# TempProbe.net
KiCad netlist of a schematic drawn in Altium Designer
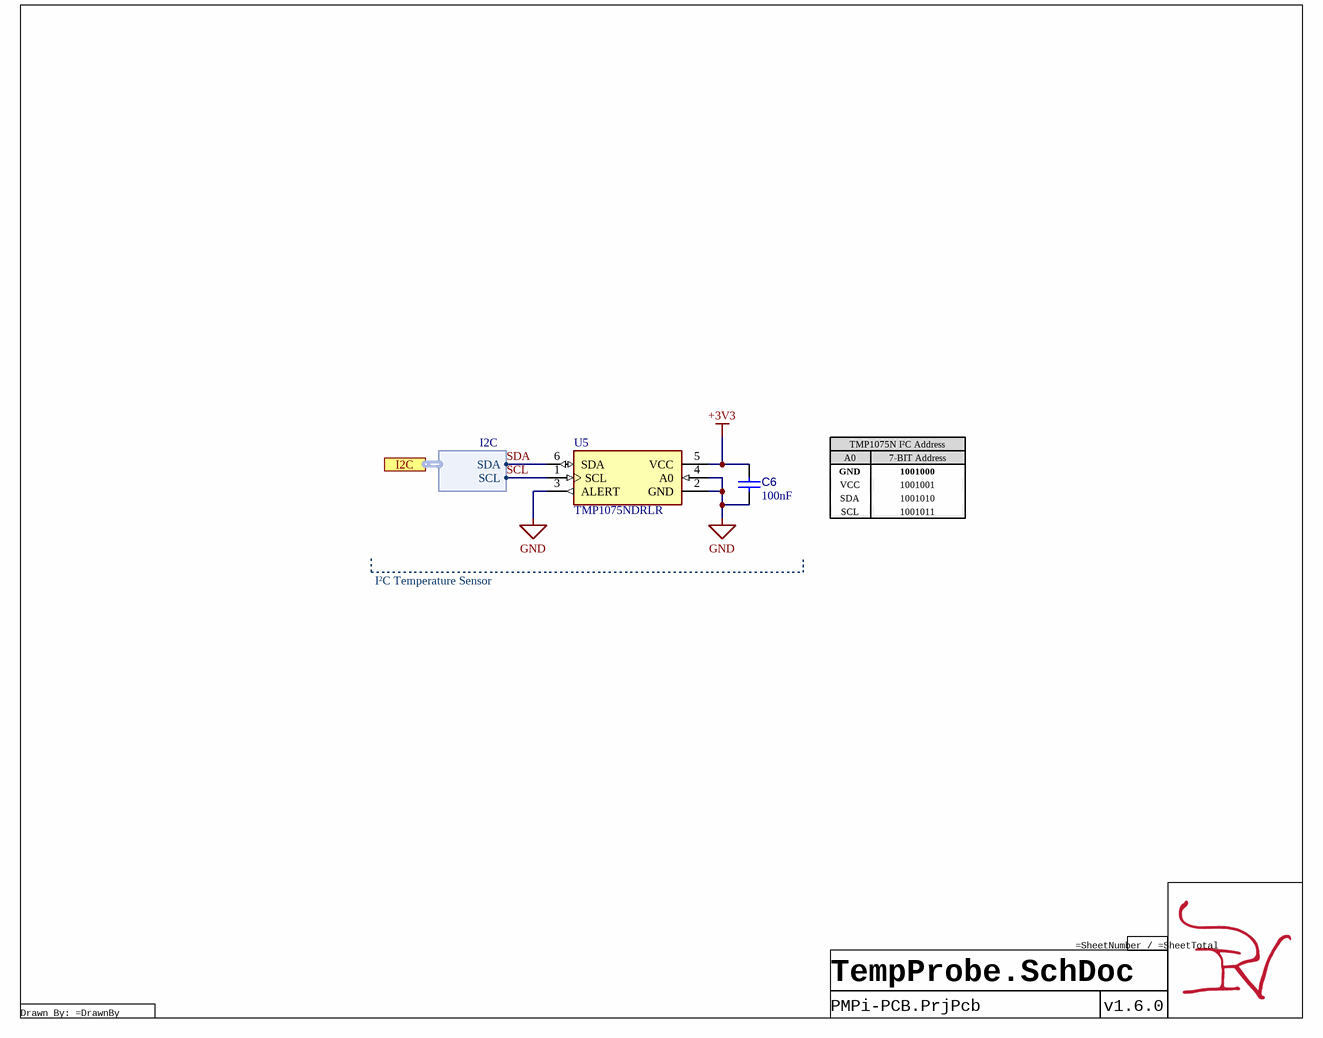
[diagram p0: TempProbe.SchDoc]

(export (version "E")
  (design (tool "Eeschema 10.0.6"))
  (components
    (comp (ref "C6")
      (value "100nF")
      (footprint "CAP 0402_1005")
      (fields (field (name "TOLERANCE") "10%") (field (name "Comment") "CAP-NP-2"))
      (libsource (lib "IIT Motorsports") (part "CAP-NP-2"))
    )
    (comp (ref "U5")
      (value "TMP1075NDRLR")
      (footprint "SOT50P160X60-6N")
      (description "Serial Switch/Digital Sensor, 12 Bit(s), 2Cel, Rectangular, 6 Pin, Surface Mount")
      (fields (field (name "MF") "{'manufacturer': u'Texas Instruments'}"))
      (libsource (lib "IIT Motorsports") (part "TMP1075NDRLR"))
    )
  )
  (nets
    (net (code "2") (name "+3V3") (class "Default")
      (node (ref "C6") (pin "2") (pinfunction "2_2") (pintype "passive"))
      (node (ref "U5") (pin "5") (pinfunction "VCC_5") (pintype "power_in"))
    )
    (net (code "3") (name "/SCL") (class "Default")
      (node (ref "U5") (pin "1") (pinfunction "SCL_1") (pintype "input"))
    )
    (net (code "4") (name "/SDA") (class "Default")
      (node (ref "U5") (pin "6") (pinfunction "SDA_6") (pintype "bidirectional"))
    )
    (net (code "6") (name "GND") (class "Default")
      (node (ref "C6") (pin "1") (pinfunction "1_1") (pintype "passive"))
      (node (ref "U5") (pin "2") (pinfunction "GND_2") (pintype "power_in"))
      (node (ref "U5") (pin "3") (pinfunction "ALERT_3") (pintype "output"))
      (node (ref "U5") (pin "4") (pinfunction "A0_4") (pintype "input"))
    )
  )
)
